# SCH_TeenyModXO.net
KiCad netlist of a schematic drawn in EasyEDA
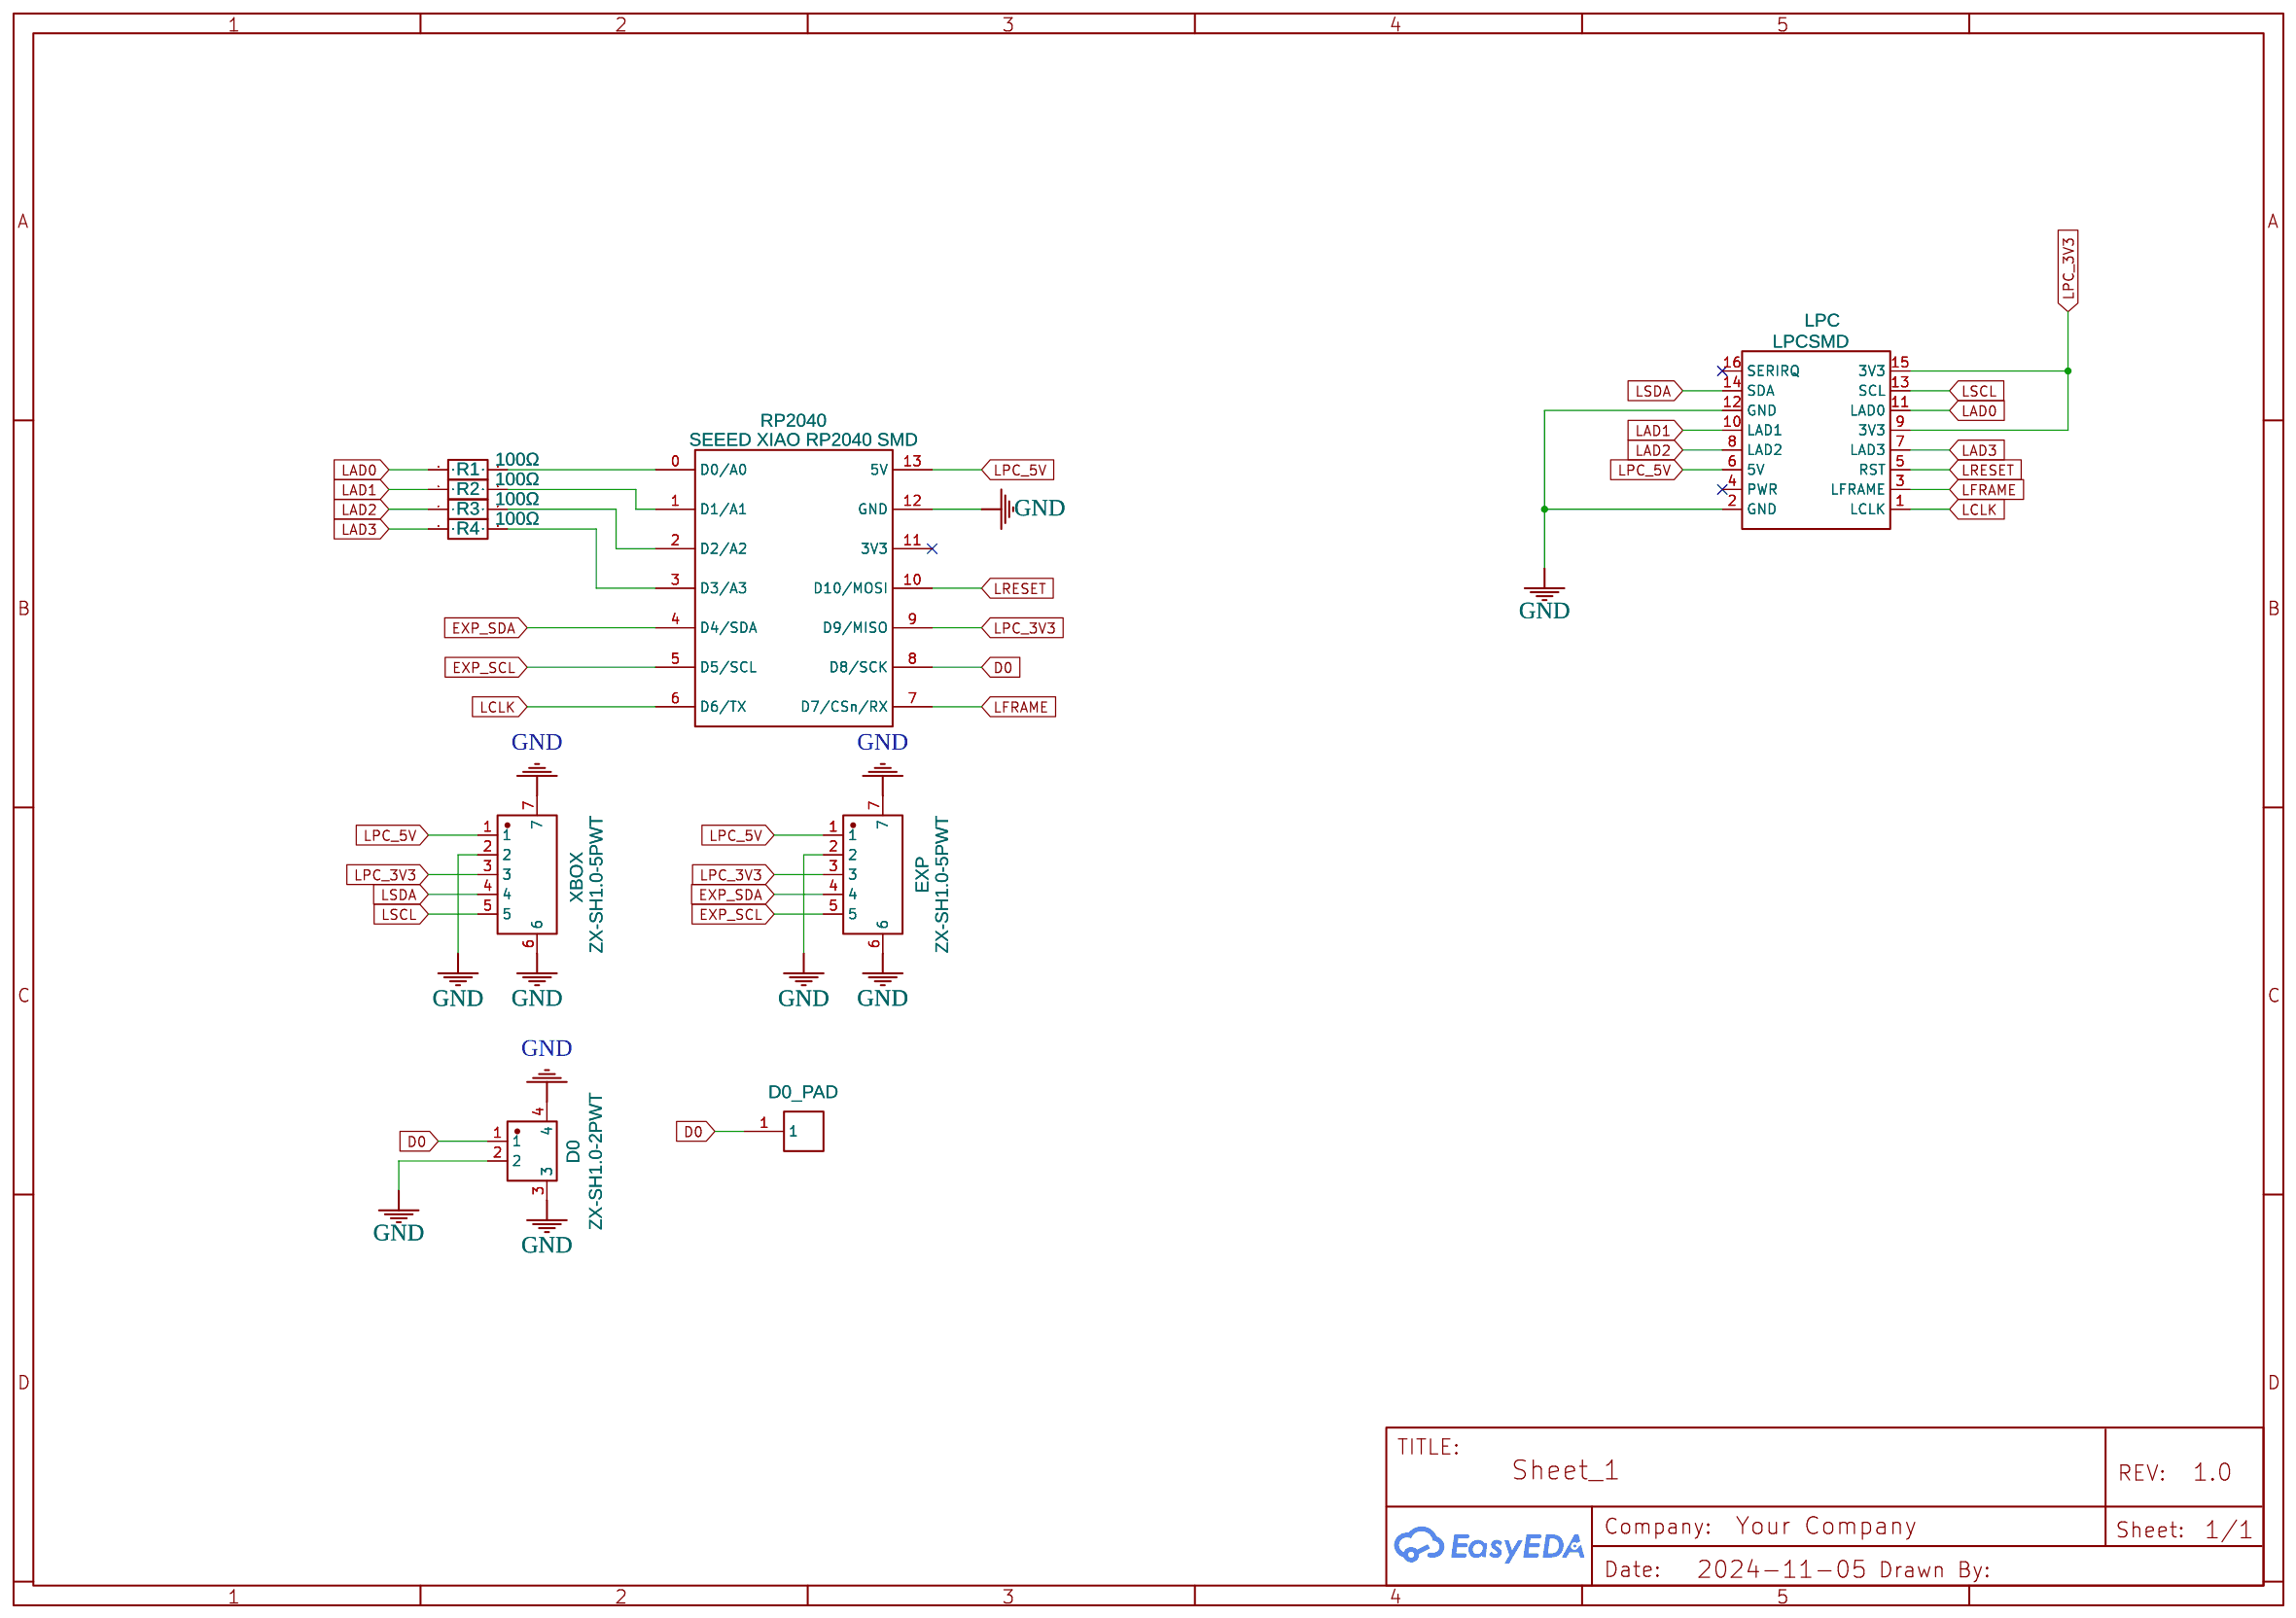
[diagram p0: schematic sheet]

(export (version "E")
  (design (tool "Eeschema 10.0.6"))
  (components
    (comp (ref "D0")
      (value "ZX-SH1.0-2PWT")
      (fields (field (name "Manufacturer") "Megastar(兆星)"))
      (libsource (lib "") (part "ZX-SH1.0-2PWT"))
    )
    (comp (ref "D0_PAD") (value "Solderpad 4x2") (libsource (lib "") (part "Solderpad 4x2")))
    (comp (ref "EXP")
      (value "ZX-SH1.0-5PWT")
      (fields (field (name "Manufacturer") "Megastar(兆星)"))
      (libsource (lib "") (part "ZX-SH1.0-5PWT"))
    )
    (comp (ref "LPC")
      (value "LPCSMD")
      (fields
        (field (name "Manufacturer Part") "HC-PM254-8.5H-2x8PS")
        (field (name "Manufacturer") "HC(虹成电子)")
      )
      (libsource (lib "") (part "LPCSMD"))
    )
    (comp (ref "R1")
      (value "100Ω")
      (fields
        (field (name "Manufacturer Part") "CRCW0603100RJNEA")
        (field (name "Manufacturer") "VISHAY(威世)")
      )
      (libsource (lib "") (part "CRCW0603100RJNEA"))
    )
    (comp (ref "R2")
      (value "100Ω")
      (fields
        (field (name "Manufacturer Part") "CRCW0603100RJNEA")
        (field (name "Manufacturer") "VISHAY(威世)")
      )
      (libsource (lib "") (part "CRCW0603100RJNEA"))
    )
    (comp (ref "R3")
      (value "100Ω")
      (fields
        (field (name "Manufacturer Part") "CRCW0603100RJNEA")
        (field (name "Manufacturer") "VISHAY(威世)")
      )
      (libsource (lib "") (part "CRCW0603100RJNEA"))
    )
    (comp (ref "R4")
      (value "100Ω")
      (fields
        (field (name "Manufacturer Part") "CRCW0603100RJNEA")
        (field (name "Manufacturer") "VISHAY(威世)")
      )
      (libsource (lib "") (part "CRCW0603100RJNEA"))
    )
    (comp (ref "RP2040") (value "SEEED XIAO RP2040 SMD") (libsource (lib "") (part "SEEED XIAO RP2040 SMD")))
    (comp (ref "XBOX")
      (value "ZX-SH1.0-5PWT")
      (fields (field (name "Manufacturer") "Megastar(兆星)"))
      (libsource (lib "") (part "ZX-SH1.0-5PWT_1"))
    )
  )
  (nets
    (net (code "1") (name "D0") (class "Default")
      (node (ref "D0") (pin "1") (pinfunction "1_1") (pintype "unspecified"))
      (node (ref "D0_PAD") (pin "1") (pinfunction "1_1") (pintype "unspecified"))
      (node (ref "RP2040") (pin "8") (pinfunction "D8/SCK_8") (pintype "unspecified"))
    )
    (net (code "2") (name "EXP_SCL") (class "Default")
      (node (ref "EXP") (pin "5") (pinfunction "5_5") (pintype "unspecified"))
      (node (ref "RP2040") (pin "5") (pinfunction "D5/SCL_5") (pintype "unspecified"))
    )
    (net (code "3") (name "EXP_SDA") (class "Default")
      (node (ref "EXP") (pin "4") (pinfunction "4_4") (pintype "unspecified"))
      (node (ref "RP2040") (pin "4") (pinfunction "D4/SDA_4") (pintype "unspecified"))
    )
    (net (code "4") (name "GND") (class "Default")
      (node (ref "D0") (pin "2") (pinfunction "2_2") (pintype "unspecified"))
      (node (ref "D0") (pin "3") (pinfunction "3_3") (pintype "unspecified"))
      (node (ref "D0") (pin "4") (pinfunction "4_4") (pintype "unspecified"))
      (node (ref "EXP") (pin "2") (pinfunction "2_2") (pintype "unspecified"))
      (node (ref "EXP") (pin "6") (pinfunction "6_6") (pintype "unspecified"))
      (node (ref "EXP") (pin "7") (pinfunction "7_7") (pintype "unspecified"))
      (node (ref "LPC") (pin "12") (pinfunction "GND_12") (pintype "unspecified"))
      (node (ref "LPC") (pin "2") (pinfunction "GND_2") (pintype "unspecified"))
      (node (ref "RP2040") (pin "12") (pinfunction "GND_12") (pintype "unspecified"))
      (node (ref "XBOX") (pin "2") (pinfunction "2_2") (pintype "unspecified"))
      (node (ref "XBOX") (pin "6") (pinfunction "6_6") (pintype "unspecified"))
      (node (ref "XBOX") (pin "7") (pinfunction "7_7") (pintype "unspecified"))
    )
    (net (code "5") (name "LAD0") (class "Default")
      (node (ref "LPC") (pin "11") (pinfunction "LAD0_11") (pintype "unspecified"))
      (node (ref "R1") (pin "1") (pinfunction "1_1") (pintype "unspecified"))
    )
    (net (code "6") (name "LAD1") (class "Default")
      (node (ref "LPC") (pin "10") (pinfunction "LAD1_10") (pintype "unspecified"))
      (node (ref "R2") (pin "1") (pinfunction "1_1") (pintype "unspecified"))
    )
    (net (code "7") (name "LAD2") (class "Default")
      (node (ref "LPC") (pin "8") (pinfunction "LAD2_8") (pintype "unspecified"))
      (node (ref "R3") (pin "1") (pinfunction "1_1") (pintype "unspecified"))
    )
    (net (code "8") (name "LAD3") (class "Default")
      (node (ref "LPC") (pin "7") (pinfunction "LAD3_7") (pintype "unspecified"))
      (node (ref "R4") (pin "1") (pinfunction "1_1") (pintype "unspecified"))
    )
    (net (code "9") (name "LCLK") (class "Default")
      (node (ref "LPC") (pin "1") (pinfunction "LCLK_1") (pintype "unspecified"))
      (node (ref "RP2040") (pin "6") (pinfunction "D6/TX_6") (pintype "unspecified"))
    )
    (net (code "10") (name "LFRAME") (class "Default")
      (node (ref "LPC") (pin "3") (pinfunction "LFRAME_3") (pintype "unspecified"))
      (node (ref "RP2040") (pin "7") (pinfunction "D7/CSn/RX_7") (pintype "unspecified"))
    )
    (net (code "11") (name "LPC_3V3") (class "Default")
      (node (ref "EXP") (pin "3") (pinfunction "3_3") (pintype "unspecified"))
      (node (ref "LPC") (pin "15") (pinfunction "3V3_15") (pintype "unspecified"))
      (node (ref "LPC") (pin "9") (pinfunction "3V3_9") (pintype "unspecified"))
      (node (ref "RP2040") (pin "9") (pinfunction "D9/MISO_9") (pintype "unspecified"))
      (node (ref "XBOX") (pin "3") (pinfunction "3_3") (pintype "unspecified"))
    )
    (net (code "12") (name "LPC_5V") (class "Default")
      (node (ref "EXP") (pin "1") (pinfunction "1_1") (pintype "unspecified"))
      (node (ref "LPC") (pin "6") (pinfunction "5V_6") (pintype "unspecified"))
      (node (ref "RP2040") (pin "13") (pinfunction "5V_13") (pintype "unspecified"))
      (node (ref "XBOX") (pin "1") (pinfunction "1_1") (pintype "unspecified"))
    )
    (net (code "13") (name "LRESET") (class "Default")
      (node (ref "LPC") (pin "5") (pinfunction "RST_5") (pintype "unspecified"))
      (node (ref "RP2040") (pin "10") (pinfunction "D10/MOSI_10") (pintype "unspecified"))
    )
    (net (code "14") (name "LSCL") (class "Default")
      (node (ref "LPC") (pin "13") (pinfunction "SCL_13") (pintype "unspecified"))
      (node (ref "XBOX") (pin "5") (pinfunction "5_5") (pintype "unspecified"))
    )
    (net (code "15") (name "LSDA") (class "Default")
      (node (ref "LPC") (pin "14") (pinfunction "SDA_14") (pintype "unspecified"))
      (node (ref "XBOX") (pin "4") (pinfunction "4_4") (pintype "unspecified"))
    )
    (net (code "16") (name "Net-(RP2040-D0{slash}A0)") (class "Default")
      (node (ref "R1") (pin "2") (pinfunction "2_2") (pintype "unspecified"))
      (node (ref "RP2040") (pin "0") (pinfunction "D0/A0_0") (pintype "unspecified"))
    )
    (net (code "17") (name "Net-(RP2040-D1{slash}A1)") (class "Default")
      (node (ref "R2") (pin "2") (pinfunction "2_2") (pintype "unspecified"))
      (node (ref "RP2040") (pin "1") (pinfunction "D1/A1_1") (pintype "unspecified"))
    )
    (net (code "18") (name "Net-(RP2040-D2{slash}A2)") (class "Default")
      (node (ref "R3") (pin "2") (pinfunction "2_2") (pintype "unspecified"))
      (node (ref "RP2040") (pin "2") (pinfunction "D2/A2_2") (pintype "unspecified"))
    )
    (net (code "19") (name "Net-(RP2040-D3{slash}A3)") (class "Default")
      (node (ref "R4") (pin "2") (pinfunction "2_2") (pintype "unspecified"))
      (node (ref "RP2040") (pin "3") (pinfunction "D3/A3_3") (pintype "unspecified"))
    )
    (net (code "20") (name "unconnected-(LPC-PWR-Pad4)") (class "Default")
      (node (ref "LPC") (pin "4") (pinfunction "PWR_4") (pintype "unspecified+no_connect"))
    )
    (net (code "21") (name "unconnected-(LPC-SERIRQ-Pad16)") (class "Default")
      (node (ref "LPC") (pin "16") (pinfunction "SERIRQ_16") (pintype "unspecified+no_connect"))
    )
    (net (code "22") (name "unconnected-(RP2040-3V3-Pad11)") (class "Default")
      (node (ref "RP2040") (pin "11") (pinfunction "3V3_11") (pintype "unspecified+no_connect"))
    )
  )
)
